# is42s32800j.net
KiCad netlist of a schematic drawn in Altium Designer
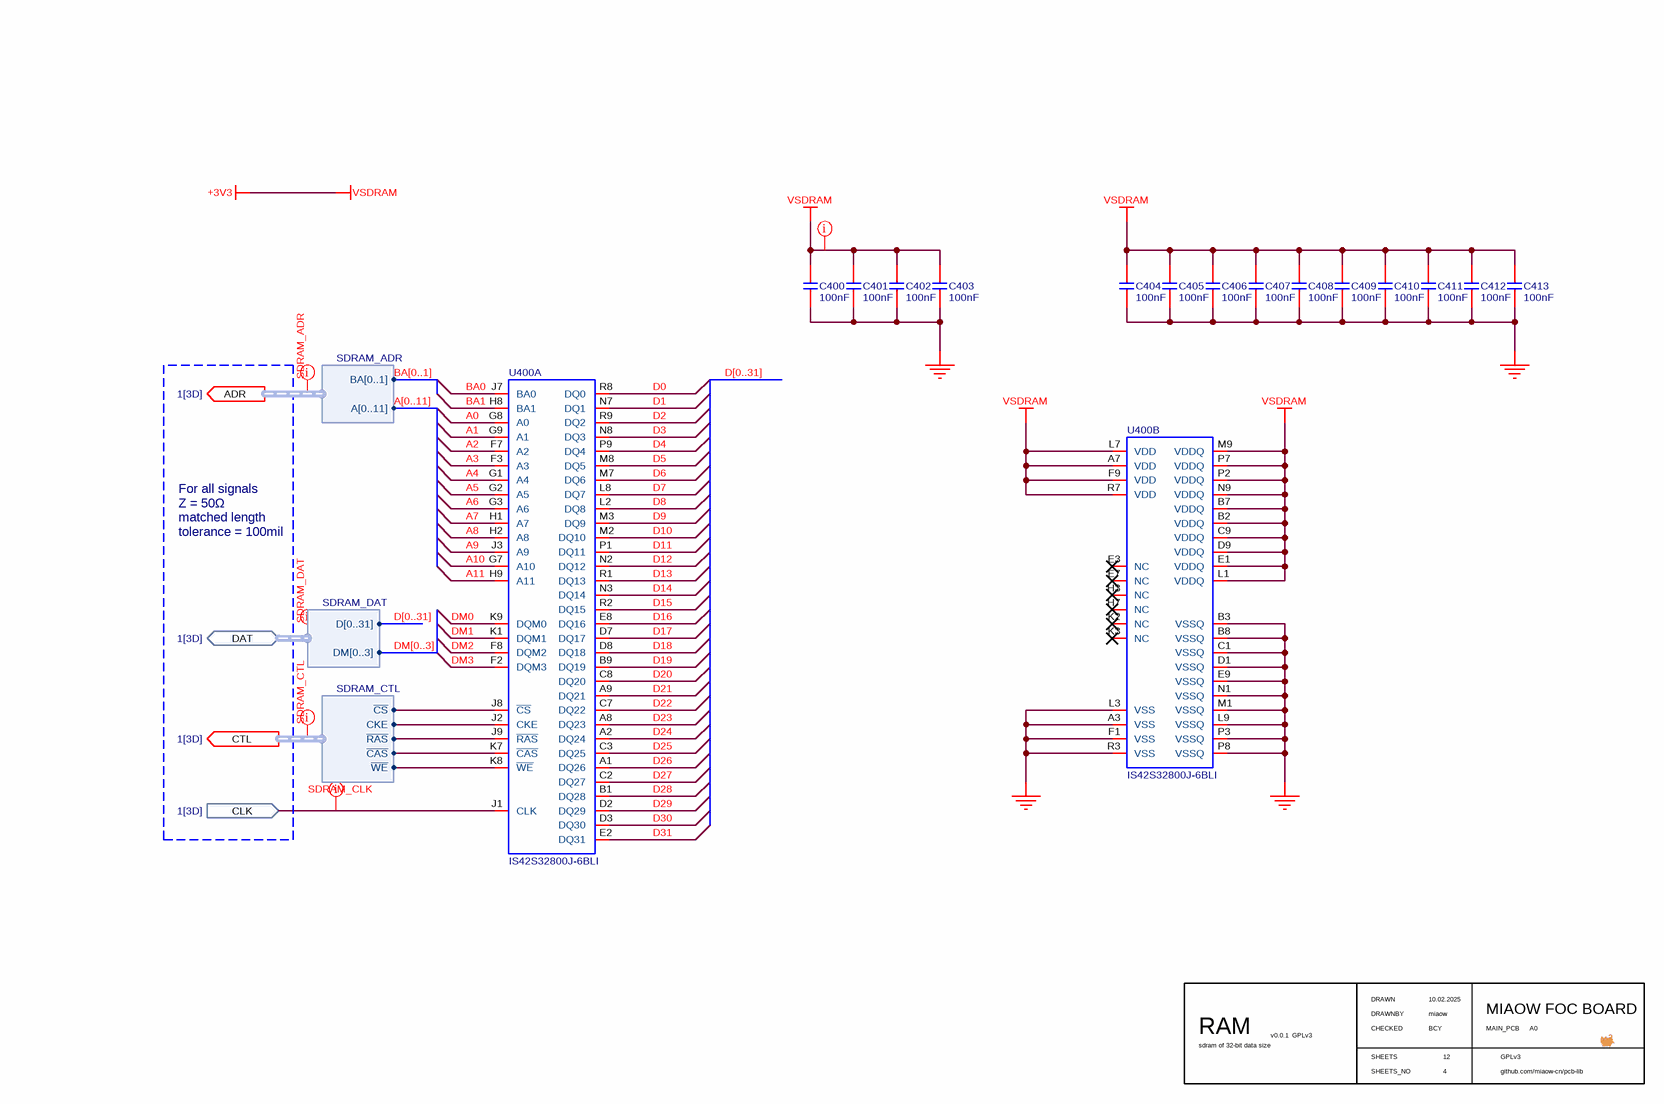
[diagram p0: is42s32800j.SchDoc]

(export (version "E")
  (design (tool "Eeschema 10.0.6"))
  (components
    (comp (ref "C400")
      (value "100nF")
      (footprint "mw:C0402")
      (fields (field (name "VOLTAGE") "25V") (field (name "Comment") "C-NOMO"))
      (libsource (lib "mw") (part "C-NOMO"))
    )
    (comp (ref "C401")
      (value "100nF")
      (footprint "mw:C0402")
      (fields (field (name "VOLTAGE") "25V") (field (name "Comment") "C-NOMO"))
      (libsource (lib "mw") (part "C-NOMO"))
    )
    (comp (ref "C402")
      (value "100nF")
      (footprint "mw:C0402")
      (fields (field (name "VOLTAGE") "25V") (field (name "Comment") "C-NOMO"))
      (libsource (lib "mw") (part "C-NOMO"))
    )
    (comp (ref "C403")
      (value "100nF")
      (footprint "mw:C0402")
      (fields (field (name "VOLTAGE") "25V") (field (name "Comment") "C-NOMO"))
      (libsource (lib "mw") (part "C-NOMO"))
    )
    (comp (ref "C404")
      (value "100nF")
      (footprint "mw:C0402")
      (fields (field (name "VOLTAGE") "25V") (field (name "Comment") "C-NOMO"))
      (libsource (lib "mw") (part "C-NOMO"))
    )
    (comp (ref "C405")
      (value "100nF")
      (footprint "mw:C0402")
      (fields (field (name "VOLTAGE") "25V") (field (name "Comment") "C-NOMO"))
      (libsource (lib "mw") (part "C-NOMO"))
    )
    (comp (ref "C406")
      (value "100nF")
      (footprint "mw:C0402")
      (fields (field (name "VOLTAGE") "25V") (field (name "Comment") "C-NOMO"))
      (libsource (lib "mw") (part "C-NOMO"))
    )
    (comp (ref "C407")
      (value "100nF")
      (footprint "mw:C0402")
      (fields (field (name "VOLTAGE") "25V") (field (name "Comment") "C-NOMO"))
      (libsource (lib "mw") (part "C-NOMO"))
    )
    (comp (ref "C408")
      (value "100nF")
      (footprint "mw:C0402")
      (fields (field (name "VOLTAGE") "25V") (field (name "Comment") "C-NOMO"))
      (libsource (lib "mw") (part "C-NOMO"))
    )
    (comp (ref "C409")
      (value "100nF")
      (footprint "mw:C0402")
      (fields (field (name "VOLTAGE") "25V") (field (name "Comment") "C-NOMO"))
      (libsource (lib "mw") (part "C-NOMO"))
    )
    (comp (ref "C410")
      (value "100nF")
      (footprint "mw:C0402")
      (fields (field (name "VOLTAGE") "25V") (field (name "Comment") "C-NOMO"))
      (libsource (lib "mw") (part "C-NOMO"))
    )
    (comp (ref "C411")
      (value "100nF")
      (footprint "mw:C0402")
      (fields (field (name "VOLTAGE") "25V") (field (name "Comment") "C-NOMO"))
      (libsource (lib "mw") (part "C-NOMO"))
    )
    (comp (ref "C412")
      (value "100nF")
      (footprint "mw:C0402")
      (fields (field (name "VOLTAGE") "25V") (field (name "Comment") "C-NOMO"))
      (libsource (lib "mw") (part "C-NOMO"))
    )
    (comp (ref "C413")
      (value "100nF")
      (footprint "mw:C0402")
      (fields (field (name "VOLTAGE") "25V") (field (name "Comment") "C-NOMO"))
      (libsource (lib "mw") (part "C-NOMO"))
    )
    (comp (ref "U400")
      (value "IS42S32800J-6BLI")
      (footprint "mw:IS42S32800J-6BLI")
      (libsource (lib "mw") (part "IS42S32800J-6BLI"))
    )
  )
  (nets
    (net (code "4") (name "+3V3") (class "Default")
      (node (ref "C400") (pin "2") (pinfunction "2_2") (pintype "passive"))
      (node (ref "C401") (pin "2") (pinfunction "2_2") (pintype "passive"))
      (node (ref "C402") (pin "2") (pinfunction "2_2") (pintype "passive"))
      (node (ref "C403") (pin "2") (pinfunction "2_2") (pintype "passive"))
      (node (ref "C404") (pin "2") (pinfunction "2_2") (pintype "passive"))
      (node (ref "C405") (pin "2") (pinfunction "2_2") (pintype "passive"))
      (node (ref "C406") (pin "2") (pinfunction "2_2") (pintype "passive"))
      (node (ref "C407") (pin "2") (pinfunction "2_2") (pintype "passive"))
      (node (ref "C408") (pin "2") (pinfunction "2_2") (pintype "passive"))
      (node (ref "C409") (pin "2") (pinfunction "2_2") (pintype "passive"))
      (node (ref "C410") (pin "2") (pinfunction "2_2") (pintype "passive"))
      (node (ref "C411") (pin "2") (pinfunction "2_2") (pintype "passive"))
      (node (ref "C412") (pin "2") (pinfunction "2_2") (pintype "passive"))
      (node (ref "C413") (pin "2") (pinfunction "2_2") (pintype "passive"))
      (node (ref "U400") (pin "A7") (pinfunction "VDD_A7") (pintype "passive"))
      (node (ref "U400") (pin "B2") (pinfunction "VDDQ_B2") (pintype "passive"))
      (node (ref "U400") (pin "B7") (pinfunction "VDDQ_B7") (pintype "passive"))
      (node (ref "U400") (pin "C9") (pinfunction "VDDQ_C9") (pintype "passive"))
      (node (ref "U400") (pin "D9") (pinfunction "VDDQ_D9") (pintype "passive"))
      (node (ref "U400") (pin "E1") (pinfunction "VDDQ_E1") (pintype "passive"))
      (node (ref "U400") (pin "F9") (pinfunction "VDD_F9") (pintype "passive"))
      (node (ref "U400") (pin "L1") (pinfunction "VDDQ_L1") (pintype "passive"))
      (node (ref "U400") (pin "L7") (pinfunction "VDD_L7") (pintype "passive"))
      (node (ref "U400") (pin "M9") (pinfunction "VDDQ_M9") (pintype "passive"))
      (node (ref "U400") (pin "N9") (pinfunction "VDDQ_N9") (pintype "passive"))
      (node (ref "U400") (pin "P2") (pinfunction "VDDQ_P2") (pintype "passive"))
      (node (ref "U400") (pin "P7") (pinfunction "VDDQ_P7") (pintype "passive"))
      (node (ref "U400") (pin "R7") (pinfunction "VDD_R7") (pintype "passive"))
    )
    (net (code "5") (name "/A0") (class "Default")
      (node (ref "U400") (pin "G8") (pinfunction "A0_G8") (pintype "passive"))
    )
    (net (code "6") (name "/A1") (class "Default")
      (node (ref "U400") (pin "G9") (pinfunction "A1_G9") (pintype "passive"))
    )
    (net (code "7") (name "/A2") (class "Default")
      (node (ref "U400") (pin "F7") (pinfunction "A2_F7") (pintype "passive"))
    )
    (net (code "8") (name "/A3") (class "Default")
      (node (ref "U400") (pin "F3") (pinfunction "A3_F3") (pintype "passive"))
    )
    (net (code "9") (name "/A4") (class "Default")
      (node (ref "U400") (pin "G1") (pinfunction "A4_G1") (pintype "passive"))
    )
    (net (code "10") (name "/A5") (class "Default")
      (node (ref "U400") (pin "G2") (pinfunction "A5_G2") (pintype "passive"))
    )
    (net (code "11") (name "/A6") (class "Default")
      (node (ref "U400") (pin "G3") (pinfunction "A6_G3") (pintype "passive"))
    )
    (net (code "12") (name "/A7") (class "Default")
      (node (ref "U400") (pin "H1") (pinfunction "A7_H1") (pintype "passive"))
    )
    (net (code "13") (name "/A8") (class "Default")
      (node (ref "U400") (pin "H2") (pinfunction "A8_H2") (pintype "passive"))
    )
    (net (code "14") (name "/A9") (class "Default")
      (node (ref "U400") (pin "J3") (pinfunction "A9_J3") (pintype "passive"))
    )
    (net (code "15") (name "/A10") (class "Default")
      (node (ref "U400") (pin "G7") (pinfunction "A10_G7") (pintype "passive"))
    )
    (net (code "16") (name "/A11") (class "Default")
      (node (ref "U400") (pin "H9") (pinfunction "A11_H9") (pintype "passive"))
    )
    (net (code "18") (name "/BA0") (class "Default")
      (node (ref "U400") (pin "J7") (pinfunction "BA0_J7") (pintype "passive"))
    )
    (net (code "19") (name "/BA1") (class "Default")
      (node (ref "U400") (pin "H8") (pinfunction "BA1_H8") (pintype "passive"))
    )
    (net (code "21") (name "/CKE") (class "Default")
      (node (ref "U400") (pin "J2") (pinfunction "CKE_J2") (pintype "passive"))
    )
    (net (code "22") (name "/CLK") (class "Default")
      (node (ref "U400") (pin "J1") (pinfunction "CLK_J1") (pintype "passive"))
    )
    (net (code "23") (name "/D0") (class "Default")
      (node (ref "U400") (pin "R8") (pinfunction "DQ0_R8") (pintype "passive"))
    )
    (net (code "24") (name "/D1") (class "Default")
      (node (ref "U400") (pin "N7") (pinfunction "DQ1_N7") (pintype "passive"))
    )
    (net (code "25") (name "/D2") (class "Default")
      (node (ref "U400") (pin "R9") (pinfunction "DQ2_R9") (pintype "passive"))
    )
    (net (code "26") (name "/D3") (class "Default")
      (node (ref "U400") (pin "N8") (pinfunction "DQ3_N8") (pintype "passive"))
    )
    (net (code "27") (name "/D4") (class "Default")
      (node (ref "U400") (pin "P9") (pinfunction "DQ4_P9") (pintype "passive"))
    )
    (net (code "28") (name "/D5") (class "Default")
      (node (ref "U400") (pin "M8") (pinfunction "DQ5_M8") (pintype "passive"))
    )
    (net (code "29") (name "/D6") (class "Default")
      (node (ref "U400") (pin "M7") (pinfunction "DQ6_M7") (pintype "passive"))
    )
    (net (code "30") (name "/D7") (class "Default")
      (node (ref "U400") (pin "L8") (pinfunction "DQ7_L8") (pintype "passive"))
    )
    (net (code "31") (name "/D8") (class "Default")
      (node (ref "U400") (pin "L2") (pinfunction "DQ8_L2") (pintype "passive"))
    )
    (net (code "32") (name "/D9") (class "Default")
      (node (ref "U400") (pin "M3") (pinfunction "DQ9_M3") (pintype "passive"))
    )
    (net (code "33") (name "/D10") (class "Default")
      (node (ref "U400") (pin "M2") (pinfunction "DQ10_M2") (pintype "passive"))
    )
    (net (code "34") (name "/D11") (class "Default")
      (node (ref "U400") (pin "P1") (pinfunction "DQ11_P1") (pintype "passive"))
    )
    (net (code "35") (name "/D12") (class "Default")
      (node (ref "U400") (pin "N2") (pinfunction "DQ12_N2") (pintype "passive"))
    )
    (net (code "36") (name "/D13") (class "Default")
      (node (ref "U400") (pin "R1") (pinfunction "DQ13_R1") (pintype "passive"))
    )
    (net (code "37") (name "/D14") (class "Default")
      (node (ref "U400") (pin "N3") (pinfunction "DQ14_N3") (pintype "passive"))
    )
    (net (code "38") (name "/D15") (class "Default")
      (node (ref "U400") (pin "R2") (pinfunction "DQ15_R2") (pintype "passive"))
    )
    (net (code "39") (name "/D16") (class "Default")
      (node (ref "U400") (pin "E8") (pinfunction "DQ16_E8") (pintype "passive"))
    )
    (net (code "40") (name "/D17") (class "Default")
      (node (ref "U400") (pin "D7") (pinfunction "DQ17_D7") (pintype "passive"))
    )
    (net (code "41") (name "/D18") (class "Default")
      (node (ref "U400") (pin "D8") (pinfunction "DQ18_D8") (pintype "passive"))
    )
    (net (code "42") (name "/D19") (class "Default")
      (node (ref "U400") (pin "B9") (pinfunction "DQ19_B9") (pintype "passive"))
    )
    (net (code "43") (name "/D20") (class "Default")
      (node (ref "U400") (pin "C8") (pinfunction "DQ20_C8") (pintype "passive"))
    )
    (net (code "44") (name "/D21") (class "Default")
      (node (ref "U400") (pin "A9") (pinfunction "DQ21_A9") (pintype "passive"))
    )
    (net (code "45") (name "/D22") (class "Default")
      (node (ref "U400") (pin "C7") (pinfunction "DQ22_C7") (pintype "passive"))
    )
    (net (code "46") (name "/D23") (class "Default")
      (node (ref "U400") (pin "A8") (pinfunction "DQ23_A8") (pintype "passive"))
    )
    (net (code "47") (name "/D24") (class "Default")
      (node (ref "U400") (pin "A2") (pinfunction "DQ24_A2") (pintype "passive"))
    )
    (net (code "48") (name "/D25") (class "Default")
      (node (ref "U400") (pin "C3") (pinfunction "DQ25_C3") (pintype "passive"))
    )
    (net (code "49") (name "/D26") (class "Default")
      (node (ref "U400") (pin "A1") (pinfunction "DQ26_A1") (pintype "passive"))
    )
    (net (code "50") (name "/D27") (class "Default")
      (node (ref "U400") (pin "C2") (pinfunction "DQ27_C2") (pintype "passive"))
    )
    (net (code "51") (name "/D28") (class "Default")
      (node (ref "U400") (pin "B1") (pinfunction "DQ28_B1") (pintype "passive"))
    )
    (net (code "52") (name "/D29") (class "Default")
      (node (ref "U400") (pin "D2") (pinfunction "DQ29_D2") (pintype "passive"))
    )
    (net (code "53") (name "/D30") (class "Default")
      (node (ref "U400") (pin "D3") (pinfunction "DQ30_D3") (pintype "passive"))
    )
    (net (code "54") (name "/D31") (class "Default")
      (node (ref "U400") (pin "E2") (pinfunction "DQ31_E2") (pintype "passive"))
    )
    (net (code "55") (name "/DM0") (class "Default")
      (node (ref "U400") (pin "K9") (pinfunction "DQM0_K9") (pintype "passive"))
    )
    (net (code "56") (name "/DM1") (class "Default")
      (node (ref "U400") (pin "K1") (pinfunction "DQM1_K1") (pintype "passive"))
    )
    (net (code "57") (name "/DM2") (class "Default")
      (node (ref "U400") (pin "F8") (pinfunction "DQM2_F8") (pintype "passive"))
    )
    (net (code "58") (name "/DM3") (class "Default")
      (node (ref "U400") (pin "F2") (pinfunction "DQM3_F2") (pintype "passive"))
    )
    (net (code "64") (name "/~{CAS}") (class "Default")
      (node (ref "U400") (pin "K7") (pinfunction "~{CAS}_K7") (pintype "passive"))
    )
    (net (code "65") (name "/~{CS}") (class "Default")
      (node (ref "U400") (pin "J8") (pinfunction "~{CS}_J8") (pintype "passive"))
    )
    (net (code "66") (name "/~{RAS}") (class "Default")
      (node (ref "U400") (pin "J9") (pinfunction "~{RAS}_J9") (pintype "passive"))
    )
    (net (code "67") (name "/~{WE}") (class "Default")
      (node (ref "U400") (pin "K8") (pinfunction "~{WE}_K8") (pintype "passive"))
    )
    (net (code "68") (name "GND") (class "Default")
      (node (ref "C400") (pin "1") (pinfunction "1_1") (pintype "passive"))
      (node (ref "C401") (pin "1") (pinfunction "1_1") (pintype "passive"))
      (node (ref "C402") (pin "1") (pinfunction "1_1") (pintype "passive"))
      (node (ref "C403") (pin "1") (pinfunction "1_1") (pintype "passive"))
      (node (ref "C404") (pin "1") (pinfunction "1_1") (pintype "passive"))
      (node (ref "C405") (pin "1") (pinfunction "1_1") (pintype "passive"))
      (node (ref "C406") (pin "1") (pinfunction "1_1") (pintype "passive"))
      (node (ref "C407") (pin "1") (pinfunction "1_1") (pintype "passive"))
      (node (ref "C408") (pin "1") (pinfunction "1_1") (pintype "passive"))
      (node (ref "C409") (pin "1") (pinfunction "1_1") (pintype "passive"))
      (node (ref "C410") (pin "1") (pinfunction "1_1") (pintype "passive"))
      (node (ref "C411") (pin "1") (pinfunction "1_1") (pintype "passive"))
      (node (ref "C412") (pin "1") (pinfunction "1_1") (pintype "passive"))
      (node (ref "C413") (pin "1") (pinfunction "1_1") (pintype "passive"))
      (node (ref "U400") (pin "A3") (pinfunction "VSS_A3") (pintype "passive"))
      (node (ref "U400") (pin "B3") (pinfunction "VSSQ_B3") (pintype "passive"))
      (node (ref "U400") (pin "B8") (pinfunction "VSSQ_B8") (pintype "passive"))
      (node (ref "U400") (pin "C1") (pinfunction "VSSQ_C1") (pintype "passive"))
      (node (ref "U400") (pin "D1") (pinfunction "VSSQ_D1") (pintype "passive"))
      (node (ref "U400") (pin "E9") (pinfunction "VSSQ_E9") (pintype "passive"))
      (node (ref "U400") (pin "F1") (pinfunction "VSS_F1") (pintype "passive"))
      (node (ref "U400") (pin "L3") (pinfunction "VSS_L3") (pintype "passive"))
      (node (ref "U400") (pin "L9") (pinfunction "VSSQ_L9") (pintype "passive"))
      (node (ref "U400") (pin "M1") (pinfunction "VSSQ_M1") (pintype "passive"))
      (node (ref "U400") (pin "N1") (pinfunction "VSSQ_N1") (pintype "passive"))
      (node (ref "U400") (pin "P3") (pinfunction "VSSQ_P3") (pintype "passive"))
      (node (ref "U400") (pin "P8") (pinfunction "VSSQ_P8") (pintype "passive"))
      (node (ref "U400") (pin "R3") (pinfunction "VSS_R3") (pintype "passive"))
    )
    (net (code "69") (name "unconnected-(U400B-NC-PadE3)") (class "Default")
      (node (ref "U400") (pin "E3") (pinfunction "NC_E3") (pintype "passive+no_connect"))
    )
    (net (code "70") (name "unconnected-(U400B-NC-PadE7)") (class "Default")
      (node (ref "U400") (pin "E7") (pinfunction "NC_E7") (pintype "passive+no_connect"))
    )
    (net (code "71") (name "unconnected-(U400B-NC-PadH3)") (class "Default")
      (node (ref "U400") (pin "H3") (pinfunction "NC_H3") (pintype "passive+no_connect"))
    )
    (net (code "72") (name "unconnected-(U400B-NC-PadH7)") (class "Default")
      (node (ref "U400") (pin "H7") (pinfunction "NC_H7") (pintype "passive+no_connect"))
    )
    (net (code "73") (name "unconnected-(U400B-NC-PadK2)") (class "Default")
      (node (ref "U400") (pin "K2") (pinfunction "NC_K2") (pintype "passive+no_connect"))
    )
    (net (code "74") (name "unconnected-(U400B-NC-PadK3)") (class "Default")
      (node (ref "U400") (pin "K3") (pinfunction "NC_K3") (pintype "passive+no_connect"))
    )
  )
)
